# SteeringWheel.net
KiCad netlist of a schematic drawn in EAGLE
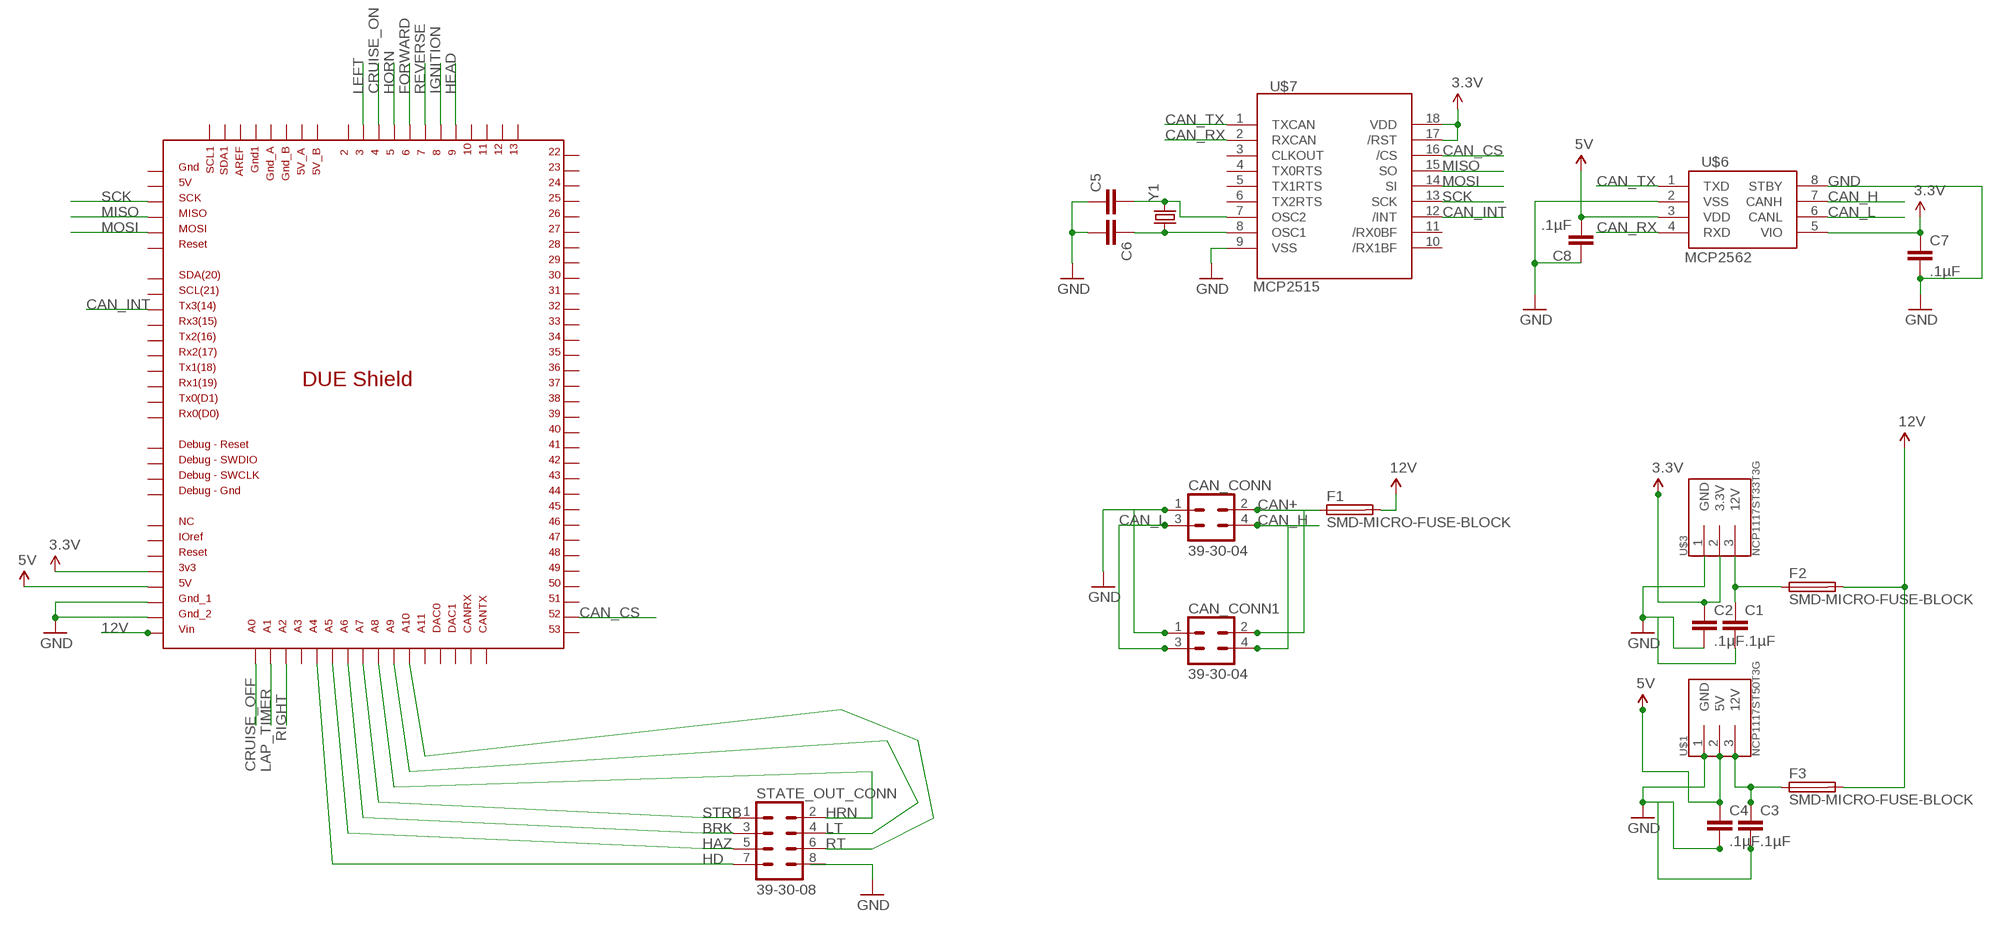
[diagram p0: schematic, sheet 1]

(export (version "E")
  (design (tool "Eeschema 10.0.6"))
  (components
    (comp (ref "C1")
      (value ".1µF")
      (footprint "eagle-import:0805")
      (libsource (lib "eagle-import") (part "CAP0805"))
    )
    (comp (ref "C2")
      (value ".1µF")
      (footprint "eagle-import:0805")
      (libsource (lib "eagle-import") (part "CAP0805"))
    )
    (comp (ref "C3")
      (value ".1µF")
      (footprint "eagle-import:0805")
      (libsource (lib "eagle-import") (part "CAP0805"))
    )
    (comp (ref "C4")
      (value ".1µF")
      (footprint "eagle-import:0805")
      (libsource (lib "eagle-import") (part "CAP0805"))
    )
    (comp (ref "C5")
      (value "CAP0805")
      (footprint "eagle-import:0805")
      (libsource (lib "eagle-import") (part "CAP0805"))
    )
    (comp (ref "C6")
      (value "CAP0805")
      (footprint "eagle-import:0805")
      (libsource (lib "eagle-import") (part "CAP0805"))
    )
    (comp (ref "C7")
      (value ".1µF")
      (footprint "eagle-import:0805")
      (libsource (lib "eagle-import") (part "CAP0805"))
    )
    (comp (ref "C8")
      (value ".1µF")
      (footprint "eagle-import:0805")
      (libsource (lib "eagle-import") (part "CAP0805"))
    )
    (comp (ref "CAN_CONN")
      (value "39-30-04")
      (footprint "eagle-import:39-30-_04_")
      (libsource (lib "eagle-import") (part "39-30-?04?"))
    )
    (comp (ref "CAN_CONN1")
      (value "39-30-04")
      (footprint "eagle-import:39-30-_04_")
      (libsource (lib "eagle-import") (part "39-30-?04?"))
    )
    (comp (ref "F1")
      (value "SMD-MICRO-FUSE-BLOCK")
      (footprint "eagle-import:OMNIBLOK")
      (libsource (lib "eagle-import") (part "SMD-MICRO-FUSE-BLOCK"))
    )
    (comp (ref "F2")
      (value "SMD-MICRO-FUSE-BLOCK")
      (footprint "eagle-import:OMNIBLOK")
      (libsource (lib "eagle-import") (part "SMD-MICRO-FUSE-BLOCK"))
    )
    (comp (ref "F3")
      (value "SMD-MICRO-FUSE-BLOCK")
      (footprint "eagle-import:OMNIBLOK")
      (libsource (lib "eagle-import") (part "SMD-MICRO-FUSE-BLOCK"))
    )
    (comp (ref "STATE_OUT_CONN")
      (value "39-30-08")
      (footprint "eagle-import:39-30-_08_")
      (libsource (lib "eagle-import") (part "39-30-?08?"))
    )
    (comp (ref "U$1")
      (value "NCP1117ST50T3G")
      (footprint "eagle-import:SOT223")
      (libsource (lib "eagle-import") (part "NCP1117ST50T3G"))
    )
    (comp (ref "U$2")
      (value "DUE(NORMAL)")
      (footprint "eagle-import:DUE(NORMAL)")
      (libsource (lib "eagle-import") (part "DUE(NORMAL)"))
    )
    (comp (ref "U$3")
      (value "NCP1117ST33T3G")
      (footprint "eagle-import:SOT223")
      (libsource (lib "eagle-import") (part "NCP1117ST33T3G"))
    )
    (comp (ref "U$6")
      (value "MCP2562")
      (footprint "eagle-import:SOIC8")
      (libsource (lib "eagle-import") (part "MCP2562"))
    )
    (comp (ref "U$7")
      (value "MCP2515")
      (footprint "eagle-import:SO-18W")
      (libsource (lib "eagle-import") (part "MCP2515"))
    )
    (comp (ref "Y1")
      (value "CRYSTALHC49US")
      (footprint "eagle-import:HC49US")
      (libsource (lib "eagle-import") (part "CRYSTALHC49US"))
    )
  )
  (nets
    (net (code "1") (name "/CAN+") (class "Default")
      (node (ref "CAN_CONN") (pin "2") (pinfunction "2_2") (pintype "passive"))
      (node (ref "CAN_CONN1") (pin "2") (pinfunction "2_2") (pintype "passive"))
      (node (ref "F1") (pin "P$1") (pinfunction "1_P$1") (pintype "passive"))
    )
    (net (code "2") (name "/CAN_CS") (class "Default")
      (node (ref "U$2") (pin "52") (pinfunction "52_52") (pintype "bidirectional"))
      (node (ref "U$7") (pin "16") (pinfunction "/CS_16") (pintype "bidirectional"))
    )
    (net (code "3") (name "/CAN_H") (class "Default")
      (node (ref "CAN_CONN") (pin "4") (pinfunction "4_4") (pintype "passive"))
      (node (ref "CAN_CONN1") (pin "4") (pinfunction "4_4") (pintype "passive"))
      (node (ref "U$6") (pin "7") (pinfunction "CANH_7") (pintype "bidirectional"))
    )
    (net (code "4") (name "/CAN_INT") (class "Default")
      (node (ref "U$2") (pin "TX3") (pinfunction "TX3_TX3") (pintype "bidirectional"))
      (node (ref "U$7") (pin "12") (pinfunction "/INT_12") (pintype "bidirectional"))
    )
    (net (code "5") (name "/CAN_L") (class "Default")
      (node (ref "CAN_CONN") (pin "3") (pinfunction "3_3") (pintype "passive"))
      (node (ref "CAN_CONN1") (pin "3") (pinfunction "3_3") (pintype "passive"))
      (node (ref "U$6") (pin "6") (pinfunction "CANL_6") (pintype "bidirectional"))
    )
    (net (code "6") (name "/CAN_RX") (class "Default")
      (node (ref "U$6") (pin "4") (pinfunction "RXD_4") (pintype "bidirectional"))
      (node (ref "U$7") (pin "2") (pinfunction "RXCAN_2") (pintype "bidirectional"))
    )
    (net (code "7") (name "/CAN_TX") (class "Default")
      (node (ref "U$6") (pin "1") (pinfunction "TXD_1") (pintype "bidirectional"))
      (node (ref "U$7") (pin "1") (pinfunction "TXCAN_1") (pintype "bidirectional"))
    )
    (net (code "8") (name "/CRUISE_OFF") (class "Default")
      (node (ref "U$2") (pin "A0") (pinfunction "A0_A0") (pintype "bidirectional"))
    )
    (net (code "9") (name "/CRUISE_ON") (class "Default")
      (node (ref "U$2") (pin "4") (pinfunction "4_4") (pintype "bidirectional"))
    )
    (net (code "10") (name "/FORWARD") (class "Default")
      (node (ref "U$2") (pin "6") (pinfunction "6_6") (pintype "bidirectional"))
    )
    (net (code "11") (name "/HEAD") (class "Default")
      (node (ref "U$2") (pin "9") (pinfunction "9_9") (pintype "bidirectional"))
    )
    (net (code "12") (name "/HORN") (class "Default")
      (node (ref "U$2") (pin "5") (pinfunction "5_5") (pintype "bidirectional"))
    )
    (net (code "13") (name "/IGNITION") (class "Default")
      (node (ref "U$2") (pin "8") (pinfunction "8_8") (pintype "bidirectional"))
    )
    (net (code "14") (name "/LAP_TIMER") (class "Default")
      (node (ref "U$2") (pin "A1") (pinfunction "A1_A1") (pintype "bidirectional"))
    )
    (net (code "15") (name "/LEFT") (class "Default")
      (node (ref "U$2") (pin "3") (pinfunction "3_3") (pintype "bidirectional"))
    )
    (net (code "16") (name "/MISO") (class "Default")
      (node (ref "U$2") (pin "MISO_ICSP") (pinfunction "MISO_ICSP_MISO_ICSP") (pintype "bidirectional"))
      (node (ref "U$7") (pin "15") (pinfunction "SO_15") (pintype "bidirectional"))
    )
    (net (code "17") (name "/MOSI") (class "Default")
      (node (ref "U$2") (pin "MOSI_ICSP") (pinfunction "MOSI_ICSP_MOSI_ICSP") (pintype "bidirectional"))
      (node (ref "U$7") (pin "14") (pinfunction "SI_14") (pintype "bidirectional"))
    )
    (net (code "18") (name "/REVERSE") (class "Default")
      (node (ref "U$2") (pin "7") (pinfunction "7_7") (pintype "bidirectional"))
    )
    (net (code "19") (name "/RIGHT") (class "Default")
      (node (ref "U$2") (pin "A2") (pinfunction "A2_A2") (pintype "bidirectional"))
    )
    (net (code "20") (name "/SCK") (class "Default")
      (node (ref "U$2") (pin "SCK_ICSP") (pinfunction "SCK_ICSP_SCK_ICSP") (pintype "bidirectional"))
      (node (ref "U$7") (pin "13") (pinfunction "SCK_13") (pintype "bidirectional"))
    )
    (net (code "21") (name "3.3V") (class "Default")
      (node (ref "C2") (pin "1") (pinfunction "1_1") (pintype "passive"))
      (node (ref "C7") (pin "1") (pinfunction "1_1") (pintype "passive"))
      (node (ref "U$2") (pin "3V3") (pinfunction "3V3_3V3") (pintype "bidirectional"))
      (node (ref "U$3") (pin "2") (pinfunction "3.3V_2") (pintype "bidirectional"))
      (node (ref "U$6") (pin "5") (pinfunction "VIO_5") (pintype "bidirectional"))
      (node (ref "U$7") (pin "17") (pinfunction "/RST_17") (pintype "bidirectional"))
      (node (ref "U$7") (pin "18") (pinfunction "VDD_18") (pintype "bidirectional"))
    )
    (net (code "22") (name "5V") (class "Default")
      (node (ref "C4") (pin "1") (pinfunction "1_1") (pintype "passive"))
      (node (ref "C8") (pin "2") (pinfunction "2_2") (pintype "passive"))
      (node (ref "U$1") (pin "2") (pinfunction "5V_2") (pintype "bidirectional"))
      (node (ref "U$2") (pin "5V") (pinfunction "5V_5V") (pintype "bidirectional"))
      (node (ref "U$6") (pin "3") (pinfunction "VDD_3") (pintype "bidirectional"))
    )
    (net (code "23") (name "12V") (class "Default")
      (node (ref "F1") (pin "P$2") (pinfunction "2_P$2") (pintype "passive"))
      (node (ref "F2") (pin "P$2") (pinfunction "2_P$2") (pintype "passive"))
      (node (ref "F3") (pin "P$2") (pinfunction "2_P$2") (pintype "passive"))
      (node (ref "U$2") (pin "VIN") (pinfunction "VIN_VIN") (pintype "bidirectional"))
    )
    (net (code "24") (name "GND") (class "Default")
      (node (ref "C1") (pin "2") (pinfunction "2_2") (pintype "passive"))
      (node (ref "C2") (pin "2") (pinfunction "2_2") (pintype "passive"))
      (node (ref "C3") (pin "2") (pinfunction "2_2") (pintype "passive"))
      (node (ref "C4") (pin "2") (pinfunction "2_2") (pintype "passive"))
      (node (ref "C5") (pin "1") (pinfunction "1_1") (pintype "passive"))
      (node (ref "C6") (pin "2") (pinfunction "2_2") (pintype "passive"))
      (node (ref "C7") (pin "2") (pinfunction "2_2") (pintype "passive"))
      (node (ref "C8") (pin "1") (pinfunction "1_1") (pintype "passive"))
      (node (ref "CAN_CONN") (pin "1") (pinfunction "1_1") (pintype "passive"))
      (node (ref "CAN_CONN1") (pin "1") (pinfunction "1_1") (pintype "passive"))
      (node (ref "U$1") (pin "1") (pinfunction "GND_1") (pintype "bidirectional"))
      (node (ref "U$2") (pin "GND_1") (pinfunction "GND_1_GND_1") (pintype "bidirectional"))
      (node (ref "U$2") (pin "GND_2") (pinfunction "GND_2_GND_2") (pintype "bidirectional"))
      (node (ref "U$3") (pin "1") (pinfunction "GND_1") (pintype "bidirectional"))
      (node (ref "U$6") (pin "2") (pinfunction "VSS_2") (pintype "bidirectional"))
      (node (ref "U$6") (pin "8") (pinfunction "STBY_8") (pintype "bidirectional"))
      (node (ref "U$7") (pin "9") (pinfunction "VSS_9") (pintype "bidirectional"))
    )
    (net (code "25") (name "Net-(F2-1)") (class "Default")
      (node (ref "C1") (pin "1") (pinfunction "1_1") (pintype "passive"))
      (node (ref "F2") (pin "P$1") (pinfunction "1_P$1") (pintype "passive"))
      (node (ref "U$3") (pin "3") (pinfunction "12V_3") (pintype "bidirectional"))
    )
    (net (code "26") (name "Net-(F3-1)") (class "Default")
      (node (ref "C3") (pin "1") (pinfunction "1_1") (pintype "passive"))
      (node (ref "F3") (pin "P$1") (pinfunction "1_P$1") (pintype "passive"))
      (node (ref "U$1") (pin "3") (pinfunction "12V_3") (pintype "bidirectional"))
    )
    (net (code "27") (name "Net-(STATE_OUT_CONN-Pad1)") (class "Default")
      (node (ref "STATE_OUT_CONN") (pin "1") (pinfunction "1_1") (pintype "passive"))
      (node (ref "U$2") (pin "A7") (pinfunction "A7_A7") (pintype "bidirectional"))
    )
    (net (code "28") (name "Net-(STATE_OUT_CONN-Pad2)") (class "Default")
      (node (ref "STATE_OUT_CONN") (pin "2") (pinfunction "2_2") (pintype "passive"))
      (node (ref "U$2") (pin "A8") (pinfunction "A8_A8") (pintype "bidirectional"))
    )
    (net (code "29") (name "Net-(STATE_OUT_CONN-Pad3)") (class "Default")
      (node (ref "STATE_OUT_CONN") (pin "3") (pinfunction "3_3") (pintype "passive"))
      (node (ref "U$2") (pin "A6") (pinfunction "A6_A6") (pintype "bidirectional"))
    )
    (net (code "30") (name "Net-(STATE_OUT_CONN-Pad4)") (class "Default")
      (node (ref "STATE_OUT_CONN") (pin "4") (pinfunction "4_4") (pintype "passive"))
      (node (ref "U$2") (pin "A9") (pinfunction "A9_A9") (pintype "bidirectional"))
    )
    (net (code "31") (name "Net-(STATE_OUT_CONN-Pad5)") (class "Default")
      (node (ref "STATE_OUT_CONN") (pin "5") (pinfunction "5_5") (pintype "passive"))
      (node (ref "U$2") (pin "A5") (pinfunction "A5_A5") (pintype "bidirectional"))
    )
    (net (code "32") (name "Net-(STATE_OUT_CONN-Pad6)") (class "Default")
      (node (ref "STATE_OUT_CONN") (pin "6") (pinfunction "6_6") (pintype "passive"))
      (node (ref "U$2") (pin "A10") (pinfunction "A10_A10") (pintype "bidirectional"))
    )
    (net (code "33") (name "Net-(STATE_OUT_CONN-Pad7)") (class "Default")
      (node (ref "STATE_OUT_CONN") (pin "7") (pinfunction "7_7") (pintype "passive"))
      (node (ref "U$2") (pin "A4") (pinfunction "A4_A4") (pintype "bidirectional"))
    )
    (net (code "34") (name "Net-(U$7-OSC1)") (class "Default")
      (node (ref "C6") (pin "1") (pinfunction "1_1") (pintype "passive"))
      (node (ref "U$7") (pin "8") (pinfunction "OSC1_8") (pintype "bidirectional"))
      (node (ref "Y1") (pin "1") (pinfunction "1_1") (pintype "passive"))
    )
    (net (code "35") (name "Net-(U$7-OSC2)") (class "Default")
      (node (ref "C5") (pin "2") (pinfunction "2_2") (pintype "passive"))
      (node (ref "U$7") (pin "7") (pinfunction "OSC2_7") (pintype "bidirectional"))
      (node (ref "Y1") (pin "2") (pinfunction "2_2") (pintype "passive"))
    )
    (net (code "36") (name "unconnected-(STATE_OUT_CONN-Pad8)") (class "Default")
      (node (ref "STATE_OUT_CONN") (pin "8") (pinfunction "8_8") (pintype "passive"))
    )
    (net (code "37") (name "unconnected-(U$2-Pad2)") (class "Default")
      (node (ref "U$2") (pin "2") (pinfunction "2_2") (pintype "bidirectional"))
    )
    (net (code "38") (name "unconnected-(U$2-Pad5V_A)") (class "Default")
      (node (ref "U$2") (pin "5V_A") (pinfunction "5V_A_5V_A") (pintype "bidirectional"))
    )
    (net (code "39") (name "unconnected-(U$2-Pad5V_B)") (class "Default")
      (node (ref "U$2") (pin "5V_B") (pinfunction "5V_B_5V_B") (pintype "bidirectional"))
    )
    (net (code "40") (name "unconnected-(U$2-Pad5V_ICSP)") (class "Default")
      (node (ref "U$2") (pin "5V_ICSP") (pinfunction "5V_ICSP_5V_ICSP") (pintype "bidirectional"))
    )
    (net (code "41") (name "unconnected-(U$2-Pad10)") (class "Default")
      (node (ref "U$2") (pin "10") (pinfunction "10_10") (pintype "bidirectional"))
    )
    (net (code "42") (name "unconnected-(U$2-Pad11)") (class "Default")
      (node (ref "U$2") (pin "11") (pinfunction "11_11") (pintype "bidirectional"))
    )
    (net (code "43") (name "unconnected-(U$2-Pad12)") (class "Default")
      (node (ref "U$2") (pin "12") (pinfunction "12_12") (pintype "bidirectional"))
    )
    (net (code "44") (name "unconnected-(U$2-Pad13)") (class "Default")
      (node (ref "U$2") (pin "13") (pinfunction "13_13") (pintype "bidirectional"))
    )
    (net (code "45") (name "unconnected-(U$2-Pad22)") (class "Default")
      (node (ref "U$2") (pin "22") (pinfunction "22_22") (pintype "bidirectional"))
    )
    (net (code "46") (name "unconnected-(U$2-Pad23)") (class "Default")
      (node (ref "U$2") (pin "23") (pinfunction "23_23") (pintype "bidirectional"))
    )
    (net (code "47") (name "unconnected-(U$2-Pad24)") (class "Default")
      (node (ref "U$2") (pin "24") (pinfunction "24_24") (pintype "bidirectional"))
    )
    (net (code "48") (name "unconnected-(U$2-Pad25)") (class "Default")
      (node (ref "U$2") (pin "25") (pinfunction "25_25") (pintype "bidirectional"))
    )
    (net (code "49") (name "unconnected-(U$2-Pad26)") (class "Default")
      (node (ref "U$2") (pin "26") (pinfunction "26_26") (pintype "bidirectional"))
    )
    (net (code "50") (name "unconnected-(U$2-Pad27)") (class "Default")
      (node (ref "U$2") (pin "27") (pinfunction "27_27") (pintype "bidirectional"))
    )
    (net (code "51") (name "unconnected-(U$2-Pad28)") (class "Default")
      (node (ref "U$2") (pin "28") (pinfunction "28_28") (pintype "bidirectional"))
    )
    (net (code "52") (name "unconnected-(U$2-Pad29)") (class "Default")
      (node (ref "U$2") (pin "29") (pinfunction "29_29") (pintype "bidirectional"))
    )
    (net (code "53") (name "unconnected-(U$2-Pad30)") (class "Default")
      (node (ref "U$2") (pin "30") (pinfunction "30_30") (pintype "bidirectional"))
    )
    (net (code "54") (name "unconnected-(U$2-Pad31)") (class "Default")
      (node (ref "U$2") (pin "31") (pinfunction "31_31") (pintype "bidirectional"))
    )
    (net (code "55") (name "unconnected-(U$2-Pad32)") (class "Default")
      (node (ref "U$2") (pin "32") (pinfunction "32_32") (pintype "bidirectional"))
    )
    (net (code "56") (name "unconnected-(U$2-Pad33)") (class "Default")
      (node (ref "U$2") (pin "33") (pinfunction "33_33") (pintype "bidirectional"))
    )
    (net (code "57") (name "unconnected-(U$2-Pad34)") (class "Default")
      (node (ref "U$2") (pin "34") (pinfunction "34_34") (pintype "bidirectional"))
    )
    (net (code "58") (name "unconnected-(U$2-Pad35)") (class "Default")
      (node (ref "U$2") (pin "35") (pinfunction "35_35") (pintype "bidirectional"))
    )
    (net (code "59") (name "unconnected-(U$2-Pad36)") (class "Default")
      (node (ref "U$2") (pin "36") (pinfunction "36_36") (pintype "bidirectional"))
    )
    (net (code "60") (name "unconnected-(U$2-Pad37)") (class "Default")
      (node (ref "U$2") (pin "37") (pinfunction "37_37") (pintype "bidirectional"))
    )
    (net (code "61") (name "unconnected-(U$2-Pad38)") (class "Default")
      (node (ref "U$2") (pin "38") (pinfunction "38_38") (pintype "bidirectional"))
    )
    (net (code "62") (name "unconnected-(U$2-Pad39)") (class "Default")
      (node (ref "U$2") (pin "39") (pinfunction "39_39") (pintype "bidirectional"))
    )
    (net (code "63") (name "unconnected-(U$2-Pad40)") (class "Default")
      (node (ref "U$2") (pin "40") (pinfunction "40_40") (pintype "bidirectional"))
    )
    (net (code "64") (name "unconnected-(U$2-Pad41)") (class "Default")
      (node (ref "U$2") (pin "41") (pinfunction "41_41") (pintype "bidirectional"))
    )
    (net (code "65") (name "unconnected-(U$2-Pad42)") (class "Default")
      (node (ref "U$2") (pin "42") (pinfunction "42_42") (pintype "bidirectional"))
    )
    (net (code "66") (name "unconnected-(U$2-Pad43)") (class "Default")
      (node (ref "U$2") (pin "43") (pinfunction "43_43") (pintype "bidirectional"))
    )
    (net (code "67") (name "unconnected-(U$2-Pad44)") (class "Default")
      (node (ref "U$2") (pin "44") (pinfunction "44_44") (pintype "bidirectional"))
    )
    (net (code "68") (name "unconnected-(U$2-Pad45)") (class "Default")
      (node (ref "U$2") (pin "45") (pinfunction "45_45") (pintype "bidirectional"))
    )
    (net (code "69") (name "unconnected-(U$2-Pad46)") (class "Default")
      (node (ref "U$2") (pin "46") (pinfunction "46_46") (pintype "bidirectional"))
    )
    (net (code "70") (name "unconnected-(U$2-Pad47)") (class "Default")
      (node (ref "U$2") (pin "47") (pinfunction "47_47") (pintype "bidirectional"))
    )
    (net (code "71") (name "unconnected-(U$2-Pad48)") (class "Default")
      (node (ref "U$2") (pin "48") (pinfunction "48_48") (pintype "bidirectional"))
    )
    (net (code "72") (name "unconnected-(U$2-Pad49)") (class "Default")
      (node (ref "U$2") (pin "49") (pinfunction "49_49") (pintype "bidirectional"))
    )
    (net (code "73") (name "unconnected-(U$2-Pad50)") (class "Default")
      (node (ref "U$2") (pin "50") (pinfunction "50_50") (pintype "bidirectional"))
    )
    (net (code "74") (name "unconnected-(U$2-Pad51)") (class "Default")
      (node (ref "U$2") (pin "51") (pinfunction "51_51") (pintype "bidirectional"))
    )
    (net (code "75") (name "unconnected-(U$2-Pad53)") (class "Default")
      (node (ref "U$2") (pin "53") (pinfunction "53_53") (pintype "bidirectional"))
    )
    (net (code "76") (name "unconnected-(U$2-PadA3)") (class "Default")
      (node (ref "U$2") (pin "A3") (pinfunction "A3_A3") (pintype "bidirectional"))
    )
    (net (code "77") (name "unconnected-(U$2-PadA11)") (class "Default")
      (node (ref "U$2") (pin "A11") (pinfunction "A11_A11") (pintype "bidirectional"))
    )
    (net (code "78") (name "unconnected-(U$2-PadAREF)") (class "Default")
      (node (ref "U$2") (pin "AREF") (pinfunction "AREF_AREF") (pintype "bidirectional"))
    )
    (net (code "79") (name "unconnected-(U$2-PadCANRX)") (class "Default")
      (node (ref "U$2") (pin "CANRX") (pinfunction "CANRX_CANRX") (pintype "bidirectional"))
    )
    (net (code "80") (name "unconnected-(U$2-PadCANTX)") (class "Default")
      (node (ref "U$2") (pin "CANTX") (pinfunction "CANTX_CANTX") (pintype "bidirectional"))
    )
    (net (code "81") (name "unconnected-(U$2-PadDAC0)") (class "Default")
      (node (ref "U$2") (pin "DAC0") (pinfunction "DAC0_DAC0") (pintype "bidirectional"))
    )
    (net (code "82") (name "unconnected-(U$2-PadDAC1)") (class "Default")
      (node (ref "U$2") (pin "DAC1") (pinfunction "DAC1_DAC1") (pintype "bidirectional"))
    )
    (net (code "83") (name "unconnected-(U$2-PadGND1)") (class "Default")
      (node (ref "U$2") (pin "GND1") (pinfunction "GND1_GND1") (pintype "bidirectional"))
    )
    (net (code "84") (name "unconnected-(U$2-PadGND_A)") (class "Default")
      (node (ref "U$2") (pin "GND_A") (pinfunction "GND_A_GND_A") (pintype "bidirectional"))
    )
    (net (code "85") (name "unconnected-(U$2-PadGND_B)") (class "Default")
      (node (ref "U$2") (pin "GND_B") (pinfunction "GND_B_GND_B") (pintype "bidirectional"))
    )
    (net (code "86") (name "unconnected-(U$2-PadGND_DEBUG)") (class "Default")
      (node (ref "U$2") (pin "GND_DEBUG") (pinfunction "GND_DEBUG_GND_DEBUG") (pintype "bidirectional"))
    )
    (net (code "87") (name "unconnected-(U$2-PadGND_ICSP)") (class "Default")
      (node (ref "U$2") (pin "GND_ICSP") (pinfunction "GND_ICSP_GND_ICSP") (pintype "bidirectional"))
    )
    (net (code "88") (name "unconnected-(U$2-PadIOREF)") (class "Default")
      (node (ref "U$2") (pin "IOREF") (pinfunction "IOREF_IOREF") (pintype "bidirectional"))
    )
    (net (code "89") (name "unconnected-(U$2-PadNC)") (class "Default")
      (node (ref "U$2") (pin "NC") (pinfunction "NC_NC") (pintype "bidirectional"))
    )
    (net (code "90") (name "unconnected-(U$2-PadRESET)") (class "Default")
      (node (ref "U$2") (pin "RESET") (pinfunction "RESET_RESET") (pintype "bidirectional"))
    )
    (net (code "91") (name "unconnected-(U$2-PadRESET_DEBUG)") (class "Default")
      (node (ref "U$2") (pin "RESET_DEBUG") (pinfunction "RESET_DEBUG_RESET_DEBUG") (pintype "bidirectional"))
    )
    (net (code "92") (name "unconnected-(U$2-PadRESET_ICSP)") (class "Default")
      (node (ref "U$2") (pin "RESET_ICSP") (pinfunction "RESET_ICSP_RESET_ICSP") (pintype "bidirectional"))
    )
    (net (code "93") (name "unconnected-(U$2-PadRX0)") (class "Default")
      (node (ref "U$2") (pin "RX0") (pinfunction "RX0_RX0") (pintype "bidirectional"))
    )
    (net (code "94") (name "unconnected-(U$2-PadRX1)") (class "Default")
      (node (ref "U$2") (pin "RX1") (pinfunction "RX1_RX1") (pintype "bidirectional"))
    )
    (net (code "95") (name "unconnected-(U$2-PadRX2)") (class "Default")
      (node (ref "U$2") (pin "RX2") (pinfunction "RX2_RX2") (pintype "bidirectional"))
    )
    (net (code "96") (name "unconnected-(U$2-PadRX3)") (class "Default")
      (node (ref "U$2") (pin "RX3") (pinfunction "RX3_RX3") (pintype "bidirectional"))
    )
    (net (code "97") (name "unconnected-(U$2-PadSCL)") (class "Default")
      (node (ref "U$2") (pin "SCL") (pinfunction "SCL_SCL") (pintype "bidirectional"))
    )
    (net (code "98") (name "unconnected-(U$2-PadSCL1)") (class "Default")
      (node (ref "U$2") (pin "SCL1") (pinfunction "SCL1_SCL1") (pintype "bidirectional"))
    )
    (net (code "99") (name "unconnected-(U$2-PadSDA)") (class "Default")
      (node (ref "U$2") (pin "SDA") (pinfunction "SDA_SDA") (pintype "bidirectional"))
    )
    (net (code "100") (name "unconnected-(U$2-PadSDA1)") (class "Default")
      (node (ref "U$2") (pin "SDA1") (pinfunction "SDA1_SDA1") (pintype "bidirectional"))
    )
    (net (code "101") (name "unconnected-(U$2-PadSWCLK_DEBUG)") (class "Default")
      (node (ref "U$2") (pin "SWCLK_DEBUG") (pinfunction "SWCLK_DEBUG_SWCLK_DEBUG") (pintype "bidirectional"))
    )
    (net (code "102") (name "unconnected-(U$2-PadSWDIO_DEBUG)") (class "Default")
      (node (ref "U$2") (pin "SWDIO_DEBUG") (pinfunction "SWDIO_DEBUG_SWDIO_DEBUG") (pintype "bidirectional"))
    )
    (net (code "103") (name "unconnected-(U$2-PadTX0)") (class "Default")
      (node (ref "U$2") (pin "TX0") (pinfunction "TX0_TX0") (pintype "bidirectional"))
    )
    (net (code "104") (name "unconnected-(U$2-PadTX1)") (class "Default")
      (node (ref "U$2") (pin "TX1") (pinfunction "TX1_TX1") (pintype "bidirectional"))
    )
    (net (code "105") (name "unconnected-(U$2-PadTX2)") (class "Default")
      (node (ref "U$2") (pin "TX2") (pinfunction "TX2_TX2") (pintype "bidirectional"))
    )
    (net (code "106") (name "unconnected-(U$7-CLKOUT-Pad3)") (class "Default")
      (node (ref "U$7") (pin "3") (pinfunction "CLKOUT_3") (pintype "bidirectional"))
    )
    (net (code "107") (name "unconnected-(U$7-TX0RTS-Pad4)") (class "Default")
      (node (ref "U$7") (pin "4") (pinfunction "TX0RTS_4") (pintype "bidirectional"))
    )
    (net (code "108") (name "unconnected-(U$7-TX1RTS-Pad5)") (class "Default")
      (node (ref "U$7") (pin "5") (pinfunction "TX1RTS_5") (pintype "bidirectional"))
    )
    (net (code "109") (name "unconnected-(U$7-TX2RTS-Pad6)") (class "Default")
      (node (ref "U$7") (pin "6") (pinfunction "TX2RTS_6") (pintype "bidirectional"))
    )
    (net (code "110") (name "unconnected-(U$7-{slash}RX0BF-Pad11)") (class "Default")
      (node (ref "U$7") (pin "11") (pinfunction "/RX0BF_11") (pintype "bidirectional"))
    )
    (net (code "111") (name "unconnected-(U$7-{slash}RX1BF-Pad10)") (class "Default")
      (node (ref "U$7") (pin "10") (pinfunction "/RX1BF_10") (pintype "bidirectional"))
    )
  )
)
